# MIPI.net
KiCad netlist of a schematic drawn in Altium Designer
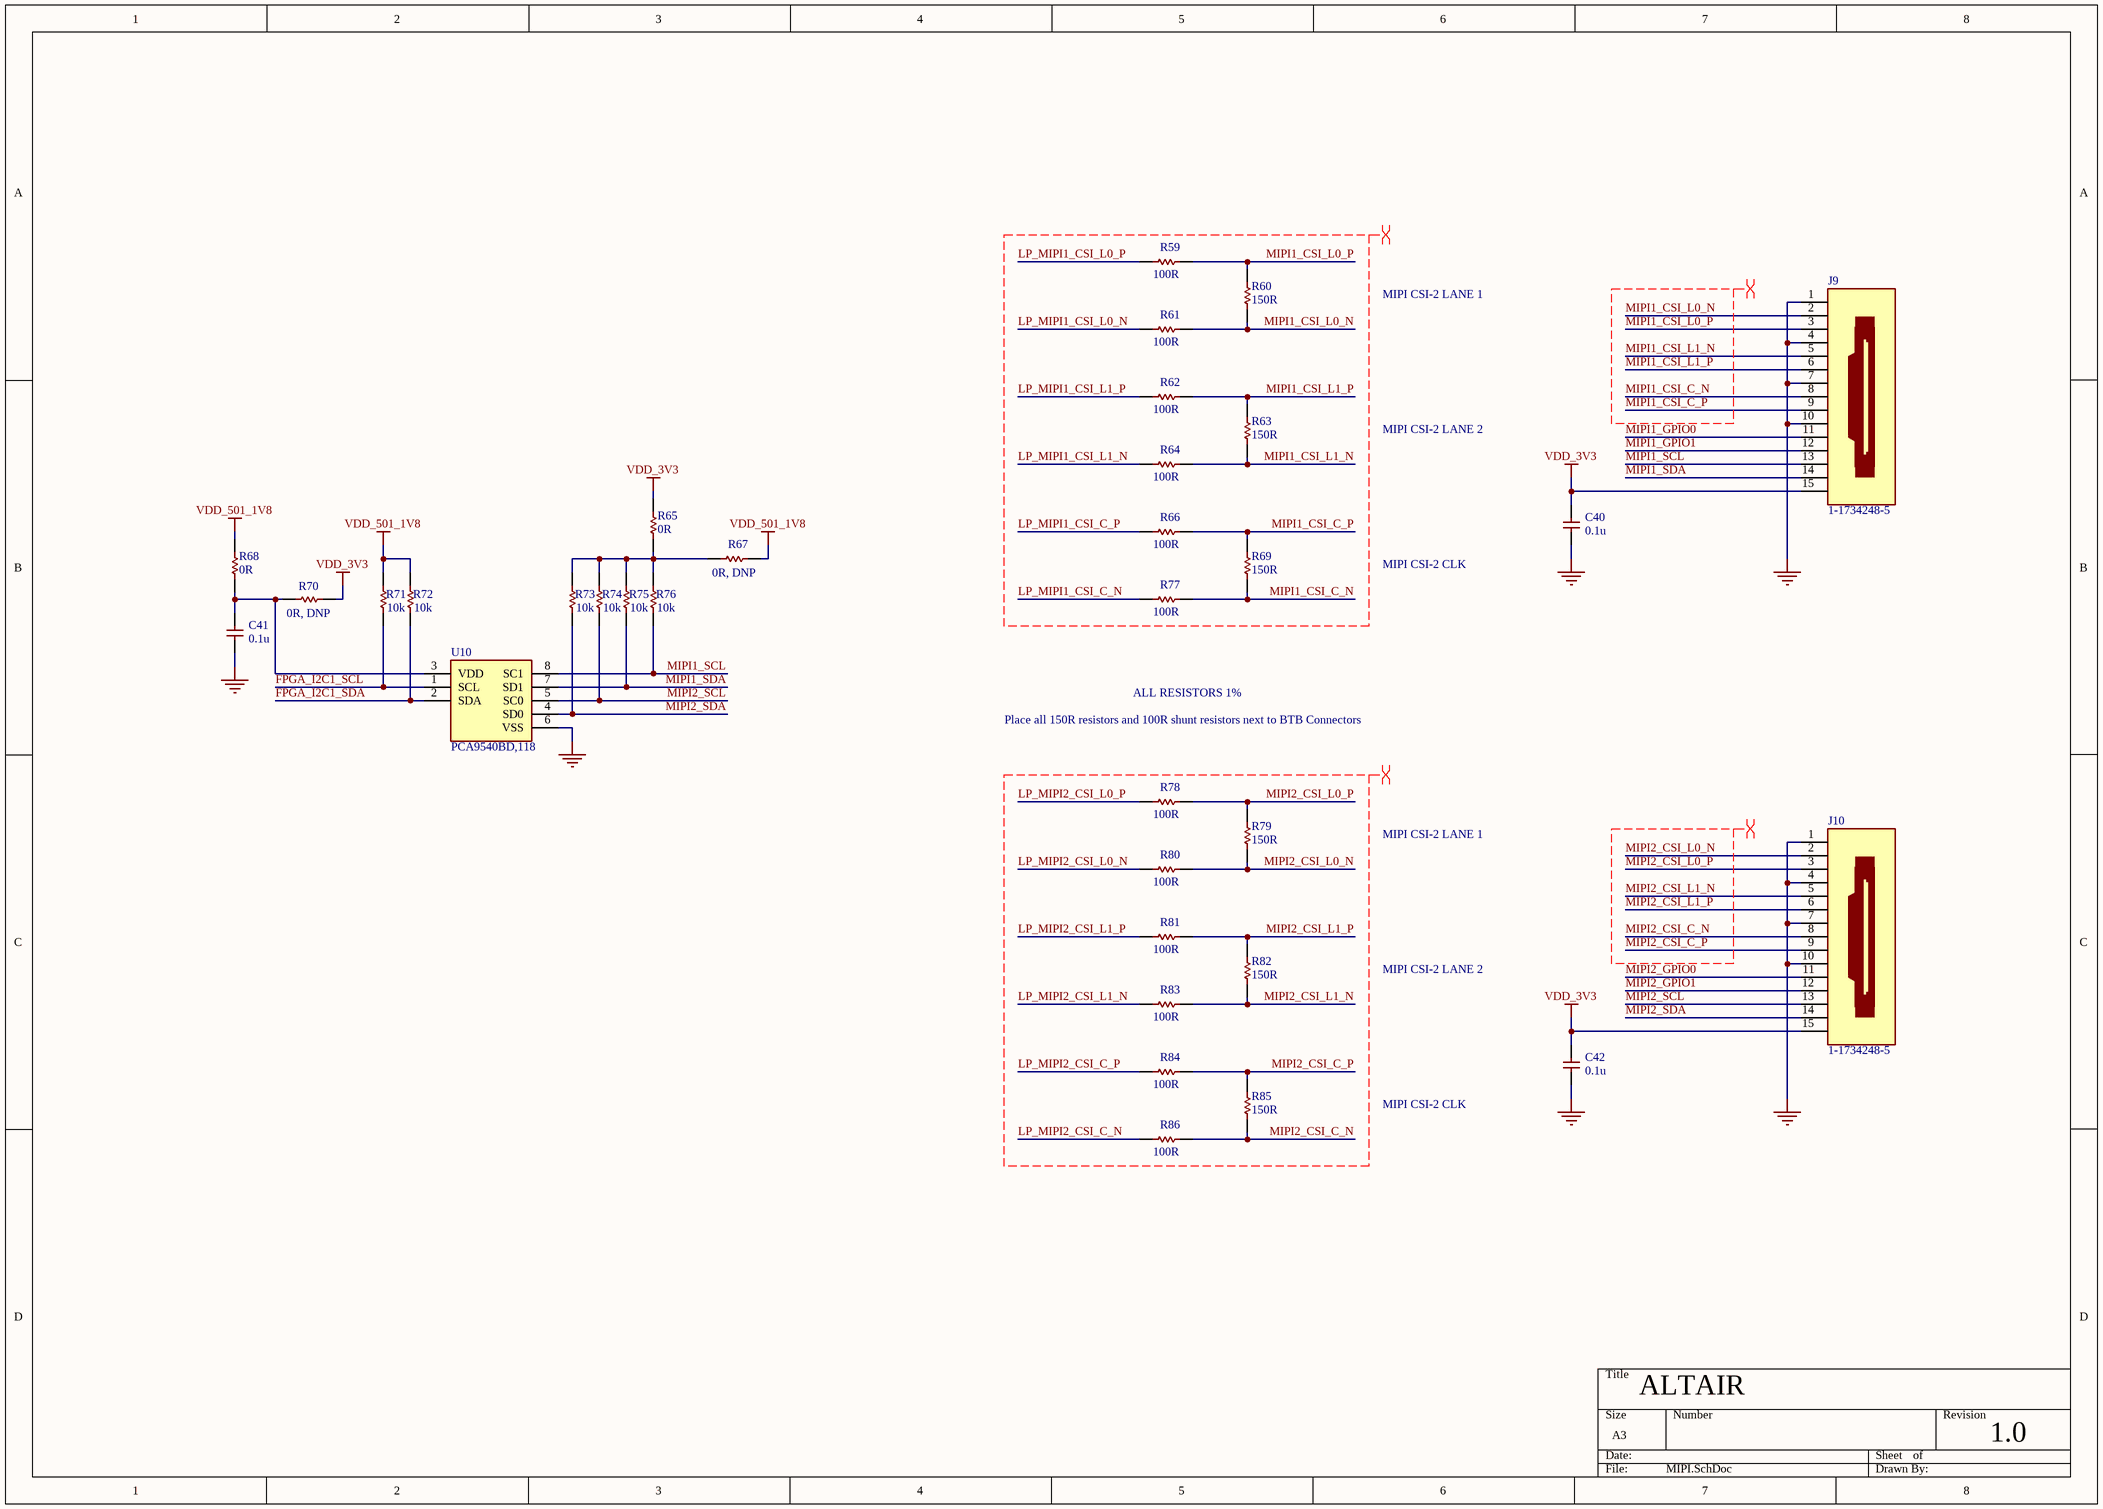
[diagram p0: MIPI.SchDoc]

(export (version "E")
  (design (tool "Eeschema 10.0.6"))
  (components
    (comp (ref "C40")
      (value "0.1u")
      (footprint "CAP_0402")
      (description "Capacitor SMD 0402")
      (fields (field (name "PART NO") "CL05B104KO5NNNC") (field (name "JLCPCB PART #") "C338112"))
      (libsource (lib "personalGenericLib") (part "CAP_0402"))
    )
    (comp (ref "C41")
      (value "0.1u")
      (footprint "CAP_0402")
      (description "Capacitor SMD 0402")
      (fields (field (name "PART NO") "CL05B104KO5NNNC") (field (name "JLCPCB PART #") "C338112"))
      (libsource (lib "personalGenericLib") (part "CAP_0402"))
    )
    (comp (ref "C42")
      (value "0.1u")
      (footprint "CAP_0402")
      (description "Capacitor SMD 0402")
      (fields (field (name "PART NO") "CL05B104KO5NNNC") (field (name "JLCPCB PART #") "C338112"))
      (libsource (lib "personalGenericLib") (part "CAP_0402"))
    )
    (comp (ref "J9")
      (value "1-1734248-5")
      (footprint "FP-1-1734248-5-MFG")
      (description "FPC CONNECTOR VERT 15 PINS 1.00MM SMD")
      (fields (field (name "JLCPCB PART #") "C2922285"))
      (libsource (lib "personalGenericLib") (part "1-1734248-5"))
    )
    (comp (ref "J10")
      (value "1-1734248-5")
      (footprint "FP-1-1734248-5-MFG")
      (description "FPC CONNECTOR VERT 15 PINS 1.00MM SMD")
      (fields (field (name "JLCPCB PART #") "C2922285"))
      (libsource (lib "personalGenericLib") (part "1-1734248-5"))
    )
    (comp (ref "R59")
      (value "100R")
      (footprint "RES_0402")
      (description "Resistor SMD 0402")
      (fields (field (name "JLCPCB PART #") "C106232") (field (name "PART NO") "RC0402FR-07100RL"))
      (libsource (lib "personalGenericLib") (part "RES_0402"))
    )
    (comp (ref "R60")
      (value "150R")
      (footprint "RES_0402")
      (description "Resistor SMD 0402")
      (fields (field (name "JLCPCB PART #") "C138054") (field (name "PART NO") "RC0402FR-07150RL"))
      (libsource (lib "personalGenericLib") (part "RES_0402"))
    )
    (comp (ref "R61")
      (value "100R")
      (footprint "RES_0402")
      (description "Resistor SMD 0402")
      (fields (field (name "JLCPCB PART #") "C106232") (field (name "PART NO") "RC0402FR-07100RL"))
      (libsource (lib "personalGenericLib") (part "RES_0402"))
    )
    (comp (ref "R62")
      (value "100R")
      (footprint "RES_0402")
      (description "Resistor SMD 0402")
      (fields (field (name "JLCPCB PART #") "C106232") (field (name "PART NO") "RC0402FR-07100RL"))
      (libsource (lib "personalGenericLib") (part "RES_0402"))
    )
    (comp (ref "R63")
      (value "150R")
      (footprint "RES_0402")
      (description "Resistor SMD 0402")
      (fields (field (name "JLCPCB PART #") "C138054") (field (name "PART NO") "RC0402FR-07150RL"))
      (libsource (lib "personalGenericLib") (part "RES_0402"))
    )
    (comp (ref "R64")
      (value "100R")
      (footprint "RES_0402")
      (description "Resistor SMD 0402")
      (fields (field (name "JLCPCB PART #") "C106232") (field (name "PART NO") "RC0402FR-07100RL"))
      (libsource (lib "personalGenericLib") (part "RES_0402"))
    )
    (comp (ref "R65")
      (value "0R")
      (footprint "RES_0402")
      (description "Resistor SMD 0402")
      (fields (field (name "JLCPCB PART #") "C60485") (field (name "PART NO") "RC0402JR-070RL"))
      (libsource (lib "personalGenericLib") (part "RES_0402"))
    )
    (comp (ref "R66")
      (value "100R")
      (footprint "RES_0402")
      (description "Resistor SMD 0402")
      (fields (field (name "JLCPCB PART #") "C106232") (field (name "PART NO") "RC0402FR-07100RL"))
      (libsource (lib "personalGenericLib") (part "RES_0402"))
    )
    (comp (ref "R67")
      (value "0R, DNP")
      (footprint "RES_0402")
      (description "Resistor SMD 0402")
      (fields (field (name "JLCPCB PART #") "C60485") (field (name "PART NO") "RC0402JR-070RL"))
      (libsource (lib "personalGenericLib") (part "RES_0402"))
    )
    (comp (ref "R68")
      (value "0R")
      (footprint "RES_0402")
      (description "Resistor SMD 0402")
      (fields (field (name "JLCPCB PART #") "C60485") (field (name "PART NO") "RC0402JR-070RL"))
      (libsource (lib "personalGenericLib") (part "RES_0402"))
    )
    (comp (ref "R69")
      (value "150R")
      (footprint "RES_0402")
      (description "Resistor SMD 0402")
      (fields (field (name "JLCPCB PART #") "C138054") (field (name "PART NO") "RC0402FR-07150RL"))
      (libsource (lib "personalGenericLib") (part "RES_0402"))
    )
    (comp (ref "R70")
      (value "0R, DNP")
      (footprint "RES_0402")
      (description "Resistor SMD 0402")
      (fields (field (name "JLCPCB PART #") "C60485") (field (name "PART NO") "RC0402JR-070RL"))
      (libsource (lib "personalGenericLib") (part "RES_0402"))
    )
    (comp (ref "R71")
      (value "10k")
      (footprint "RES_0402")
      (description "Resistor SMD 0402")
      (fields (field (name "JLCPCB PART #") "C60489") (field (name "PART NO") "RC0402JR-0710KL"))
      (libsource (lib "personalGenericLib") (part "RES_0402"))
    )
    (comp (ref "R72")
      (value "10k")
      (footprint "RES_0402")
      (description "Resistor SMD 0402")
      (fields (field (name "JLCPCB PART #") "C60489") (field (name "PART NO") "RC0402JR-0710KL"))
      (libsource (lib "personalGenericLib") (part "RES_0402"))
    )
    (comp (ref "R73")
      (value "10k")
      (footprint "RES_0402")
      (description "Resistor SMD 0402")
      (fields (field (name "JLCPCB PART #") "C60489") (field (name "PART NO") "RC0402JR-0710KL"))
      (libsource (lib "personalGenericLib") (part "RES_0402"))
    )
    (comp (ref "R74")
      (value "10k")
      (footprint "RES_0402")
      (description "Resistor SMD 0402")
      (fields (field (name "JLCPCB PART #") "C60489") (field (name "PART NO") "RC0402JR-0710KL"))
      (libsource (lib "personalGenericLib") (part "RES_0402"))
    )
    (comp (ref "R75")
      (value "10k")
      (footprint "RES_0402")
      (description "Resistor SMD 0402")
      (fields (field (name "JLCPCB PART #") "C60489") (field (name "PART NO") "RC0402JR-0710KL"))
      (libsource (lib "personalGenericLib") (part "RES_0402"))
    )
    (comp (ref "R76")
      (value "10k")
      (footprint "RES_0402")
      (description "Resistor SMD 0402")
      (fields (field (name "JLCPCB PART #") "C60489") (field (name "PART NO") "RC0402JR-0710KL"))
      (libsource (lib "personalGenericLib") (part "RES_0402"))
    )
    (comp (ref "R77")
      (value "100R")
      (footprint "RES_0402")
      (description "Resistor SMD 0402")
      (fields (field (name "JLCPCB PART #") "C106232") (field (name "PART NO") "RC0402FR-07100RL"))
      (libsource (lib "personalGenericLib") (part "RES_0402"))
    )
    (comp (ref "R78")
      (value "100R")
      (footprint "RES_0402")
      (description "Resistor SMD 0402")
      (fields (field (name "JLCPCB PART #") "C106232") (field (name "PART NO") "RC0402FR-07100RL"))
      (libsource (lib "personalGenericLib") (part "RES_0402"))
    )
    (comp (ref "R79")
      (value "150R")
      (footprint "RES_0402")
      (description "Resistor SMD 0402")
      (fields (field (name "JLCPCB PART #") "C138054") (field (name "PART NO") "RC0402FR-07150RL"))
      (libsource (lib "personalGenericLib") (part "RES_0402"))
    )
    (comp (ref "R80")
      (value "100R")
      (footprint "RES_0402")
      (description "Resistor SMD 0402")
      (fields (field (name "JLCPCB PART #") "C106232") (field (name "PART NO") "RC0402FR-07100RL"))
      (libsource (lib "personalGenericLib") (part "RES_0402"))
    )
    (comp (ref "R81")
      (value "100R")
      (footprint "RES_0402")
      (description "Resistor SMD 0402")
      (fields (field (name "JLCPCB PART #") "C106232") (field (name "PART NO") "RC0402FR-07100RL"))
      (libsource (lib "personalGenericLib") (part "RES_0402"))
    )
    (comp (ref "R82")
      (value "150R")
      (footprint "RES_0402")
      (description "Resistor SMD 0402")
      (fields (field (name "JLCPCB PART #") "C138054") (field (name "PART NO") "RC0402FR-07150RL"))
      (libsource (lib "personalGenericLib") (part "RES_0402"))
    )
    (comp (ref "R83")
      (value "100R")
      (footprint "RES_0402")
      (description "Resistor SMD 0402")
      (fields (field (name "JLCPCB PART #") "C106232") (field (name "PART NO") "RC0402FR-07100RL"))
      (libsource (lib "personalGenericLib") (part "RES_0402"))
    )
    (comp (ref "R84")
      (value "100R")
      (footprint "RES_0402")
      (description "Resistor SMD 0402")
      (fields (field (name "JLCPCB PART #") "C106232") (field (name "PART NO") "RC0402FR-07100RL"))
      (libsource (lib "personalGenericLib") (part "RES_0402"))
    )
    (comp (ref "R85")
      (value "150R")
      (footprint "RES_0402")
      (description "Resistor SMD 0402")
      (fields (field (name "JLCPCB PART #") "C138054") (field (name "PART NO") "RC0402FR-07150RL"))
      (libsource (lib "personalGenericLib") (part "RES_0402"))
    )
    (comp (ref "R86")
      (value "100R")
      (footprint "RES_0402")
      (description "Resistor SMD 0402")
      (fields (field (name "JLCPCB PART #") "C106232") (field (name "PART NO") "RC0402FR-07100RL"))
      (libsource (lib "personalGenericLib") (part "RES_0402"))
    )
    (comp (ref "U10")
      (value "PCA9540BD,118")
      (footprint "SOIC127P600X175-8N")
      (description "Integrated Circuit")
      (fields (field (name "JLCPCB PART #") "C2674107"))
      (libsource (lib "personalGenericLib") (part "PCA9540BD,118"))
    )
  )
  (nets
    (net (code "1") (name "/FPGA_I2C1_SCL") (class "Default")
      (node (ref "R71") (pin "2") (pinfunction "2_2") (pintype "passive"))
      (node (ref "U10") (pin "1") (pinfunction "SCL_1") (pintype "passive"))
    )
    (net (code "2") (name "/FPGA_I2C1_SDA") (class "Default")
      (node (ref "R72") (pin "2") (pinfunction "2_2") (pintype "passive"))
      (node (ref "U10") (pin "2") (pinfunction "SDA_2") (pintype "passive"))
    )
    (net (code "3") (name "/LP_MIPI1_CSI_C_N") (class "Default")
      (node (ref "R77") (pin "1") (pinfunction "1_1") (pintype "passive"))
    )
    (net (code "4") (name "/LP_MIPI1_CSI_C_P") (class "Default")
      (node (ref "R66") (pin "1") (pinfunction "1_1") (pintype "passive"))
    )
    (net (code "5") (name "/LP_MIPI1_CSI_L0_N") (class "Default")
      (node (ref "R61") (pin "1") (pinfunction "1_1") (pintype "passive"))
    )
    (net (code "6") (name "/LP_MIPI1_CSI_L0_P") (class "Default")
      (node (ref "R59") (pin "1") (pinfunction "1_1") (pintype "passive"))
    )
    (net (code "7") (name "/LP_MIPI1_CSI_L1_N") (class "Default")
      (node (ref "R64") (pin "1") (pinfunction "1_1") (pintype "passive"))
    )
    (net (code "8") (name "/LP_MIPI1_CSI_L1_P") (class "Default")
      (node (ref "R62") (pin "1") (pinfunction "1_1") (pintype "passive"))
    )
    (net (code "9") (name "/LP_MIPI2_CSI_C_N") (class "Default")
      (node (ref "R86") (pin "1") (pinfunction "1_1") (pintype "passive"))
    )
    (net (code "10") (name "/LP_MIPI2_CSI_C_P") (class "Default")
      (node (ref "R84") (pin "1") (pinfunction "1_1") (pintype "passive"))
    )
    (net (code "11") (name "/LP_MIPI2_CSI_L0_N") (class "Default")
      (node (ref "R80") (pin "1") (pinfunction "1_1") (pintype "passive"))
    )
    (net (code "12") (name "/LP_MIPI2_CSI_L0_P") (class "Default")
      (node (ref "R78") (pin "1") (pinfunction "1_1") (pintype "passive"))
    )
    (net (code "13") (name "/LP_MIPI2_CSI_L1_N") (class "Default")
      (node (ref "R83") (pin "1") (pinfunction "1_1") (pintype "passive"))
    )
    (net (code "14") (name "/LP_MIPI2_CSI_L1_P") (class "Default")
      (node (ref "R81") (pin "1") (pinfunction "1_1") (pintype "passive"))
    )
    (net (code "15") (name "/MIPI1_CSI_C_N") (class "Default")
      (node (ref "J9") (pin "8") (pinfunction "8_8") (pintype "passive"))
      (node (ref "R69") (pin "2") (pinfunction "2_2") (pintype "passive"))
      (node (ref "R77") (pin "2") (pinfunction "2_2") (pintype "passive"))
    )
    (net (code "16") (name "/MIPI1_CSI_C_P") (class "Default")
      (node (ref "J9") (pin "9") (pinfunction "9_9") (pintype "passive"))
      (node (ref "R66") (pin "2") (pinfunction "2_2") (pintype "passive"))
      (node (ref "R69") (pin "1") (pinfunction "1_1") (pintype "passive"))
    )
    (net (code "17") (name "/MIPI1_CSI_L0_N") (class "Default")
      (node (ref "J9") (pin "2") (pinfunction "2_2") (pintype "passive"))
      (node (ref "R60") (pin "2") (pinfunction "2_2") (pintype "passive"))
      (node (ref "R61") (pin "2") (pinfunction "2_2") (pintype "passive"))
    )
    (net (code "18") (name "/MIPI1_CSI_L0_P") (class "Default")
      (node (ref "J9") (pin "3") (pinfunction "3_3") (pintype "passive"))
      (node (ref "R59") (pin "2") (pinfunction "2_2") (pintype "passive"))
      (node (ref "R60") (pin "1") (pinfunction "1_1") (pintype "passive"))
    )
    (net (code "19") (name "/MIPI1_CSI_L1_N") (class "Default")
      (node (ref "J9") (pin "5") (pinfunction "5_5") (pintype "passive"))
      (node (ref "R63") (pin "2") (pinfunction "2_2") (pintype "passive"))
      (node (ref "R64") (pin "2") (pinfunction "2_2") (pintype "passive"))
    )
    (net (code "20") (name "/MIPI1_CSI_L1_P") (class "Default")
      (node (ref "J9") (pin "6") (pinfunction "6_6") (pintype "passive"))
      (node (ref "R62") (pin "2") (pinfunction "2_2") (pintype "passive"))
      (node (ref "R63") (pin "1") (pinfunction "1_1") (pintype "passive"))
    )
    (net (code "21") (name "/MIPI1_GPIO0") (class "Default")
      (node (ref "J9") (pin "11") (pinfunction "11_11") (pintype "passive"))
    )
    (net (code "22") (name "/MIPI1_GPIO1") (class "Default")
      (node (ref "J9") (pin "12") (pinfunction "12_12") (pintype "passive"))
    )
    (net (code "23") (name "/MIPI1_SCL") (class "Default")
      (node (ref "J9") (pin "13") (pinfunction "13_13") (pintype "passive"))
      (node (ref "R76") (pin "2") (pinfunction "2_2") (pintype "passive"))
      (node (ref "U10") (pin "8") (pinfunction "SC1_8") (pintype "passive"))
    )
    (net (code "24") (name "/MIPI1_SDA") (class "Default")
      (node (ref "J9") (pin "14") (pinfunction "14_14") (pintype "passive"))
      (node (ref "R75") (pin "2") (pinfunction "2_2") (pintype "passive"))
      (node (ref "U10") (pin "7") (pinfunction "SD1_7") (pintype "passive"))
    )
    (net (code "25") (name "/MIPI2_CSI_C_N") (class "Default")
      (node (ref "J10") (pin "8") (pinfunction "8_8") (pintype "passive"))
      (node (ref "R85") (pin "2") (pinfunction "2_2") (pintype "passive"))
      (node (ref "R86") (pin "2") (pinfunction "2_2") (pintype "passive"))
    )
    (net (code "26") (name "/MIPI2_CSI_C_P") (class "Default")
      (node (ref "J10") (pin "9") (pinfunction "9_9") (pintype "passive"))
      (node (ref "R84") (pin "2") (pinfunction "2_2") (pintype "passive"))
      (node (ref "R85") (pin "1") (pinfunction "1_1") (pintype "passive"))
    )
    (net (code "27") (name "/MIPI2_CSI_L0_N") (class "Default")
      (node (ref "J10") (pin "2") (pinfunction "2_2") (pintype "passive"))
      (node (ref "R79") (pin "2") (pinfunction "2_2") (pintype "passive"))
      (node (ref "R80") (pin "2") (pinfunction "2_2") (pintype "passive"))
    )
    (net (code "28") (name "/MIPI2_CSI_L0_P") (class "Default")
      (node (ref "J10") (pin "3") (pinfunction "3_3") (pintype "passive"))
      (node (ref "R78") (pin "2") (pinfunction "2_2") (pintype "passive"))
      (node (ref "R79") (pin "1") (pinfunction "1_1") (pintype "passive"))
    )
    (net (code "29") (name "/MIPI2_CSI_L1_N") (class "Default")
      (node (ref "J10") (pin "5") (pinfunction "5_5") (pintype "passive"))
      (node (ref "R82") (pin "2") (pinfunction "2_2") (pintype "passive"))
      (node (ref "R83") (pin "2") (pinfunction "2_2") (pintype "passive"))
    )
    (net (code "30") (name "/MIPI2_CSI_L1_P") (class "Default")
      (node (ref "J10") (pin "6") (pinfunction "6_6") (pintype "passive"))
      (node (ref "R81") (pin "2") (pinfunction "2_2") (pintype "passive"))
      (node (ref "R82") (pin "1") (pinfunction "1_1") (pintype "passive"))
    )
    (net (code "31") (name "/MIPI2_GPIO0") (class "Default")
      (node (ref "J10") (pin "11") (pinfunction "11_11") (pintype "passive"))
    )
    (net (code "32") (name "/MIPI2_GPIO1") (class "Default")
      (node (ref "J10") (pin "12") (pinfunction "12_12") (pintype "passive"))
    )
    (net (code "33") (name "/MIPI2_SCL") (class "Default")
      (node (ref "J10") (pin "13") (pinfunction "13_13") (pintype "passive"))
      (node (ref "R74") (pin "2") (pinfunction "2_2") (pintype "passive"))
      (node (ref "U10") (pin "5") (pinfunction "SC0_5") (pintype "passive"))
    )
    (net (code "34") (name "/MIPI2_SDA") (class "Default")
      (node (ref "J10") (pin "14") (pinfunction "14_14") (pintype "passive"))
      (node (ref "R73") (pin "2") (pinfunction "2_2") (pintype "passive"))
      (node (ref "U10") (pin "4") (pinfunction "SD0_4") (pintype "passive"))
    )
    (net (code "35") (name "GND") (class "Default")
      (node (ref "C40") (pin "1") (pinfunction "1_1") (pintype "passive"))
      (node (ref "C41") (pin "1") (pinfunction "1_1") (pintype "passive"))
      (node (ref "C42") (pin "1") (pinfunction "1_1") (pintype "passive"))
      (node (ref "J10") (pin "1") (pinfunction "1_1") (pintype "passive"))
      (node (ref "J10") (pin "10") (pinfunction "10_10") (pintype "passive"))
      (node (ref "J10") (pin "4") (pinfunction "4_4") (pintype "passive"))
      (node (ref "J10") (pin "7") (pinfunction "7_7") (pintype "passive"))
      (node (ref "J9") (pin "1") (pinfunction "1_1") (pintype "passive"))
      (node (ref "J9") (pin "10") (pinfunction "10_10") (pintype "passive"))
      (node (ref "J9") (pin "4") (pinfunction "4_4") (pintype "passive"))
      (node (ref "J9") (pin "7") (pinfunction "7_7") (pintype "passive"))
      (node (ref "U10") (pin "6") (pinfunction "VSS_6") (pintype "passive"))
    )
    (net (code "36") (name "Net-(R65-Pad1)") (class "Default")
      (node (ref "R65") (pin "1") (pinfunction "1_1") (pintype "passive"))
      (node (ref "R67") (pin "1") (pinfunction "1_1") (pintype "passive"))
      (node (ref "R73") (pin "1") (pinfunction "1_1") (pintype "passive"))
      (node (ref "R74") (pin "1") (pinfunction "1_1") (pintype "passive"))
      (node (ref "R75") (pin "1") (pinfunction "1_1") (pintype "passive"))
      (node (ref "R76") (pin "1") (pinfunction "1_1") (pintype "passive"))
    )
    (net (code "37") (name "Net-(U10-VDD)") (class "Default")
      (node (ref "C41") (pin "2") (pinfunction "2_2") (pintype "passive"))
      (node (ref "R68") (pin "1") (pinfunction "1_1") (pintype "passive"))
      (node (ref "R70") (pin "1") (pinfunction "1_1") (pintype "passive"))
      (node (ref "U10") (pin "3") (pinfunction "VDD_3") (pintype "passive"))
    )
    (net (code "38") (name "VDD_3V3") (class "Default")
      (node (ref "C40") (pin "2") (pinfunction "2_2") (pintype "passive"))
      (node (ref "C42") (pin "2") (pinfunction "2_2") (pintype "passive"))
      (node (ref "J10") (pin "15") (pinfunction "15_15") (pintype "passive"))
      (node (ref "J9") (pin "15") (pinfunction "15_15") (pintype "passive"))
      (node (ref "R65") (pin "2") (pinfunction "2_2") (pintype "passive"))
      (node (ref "R70") (pin "2") (pinfunction "2_2") (pintype "passive"))
    )
    (net (code "39") (name "VDD_501_1V8") (class "Default")
      (node (ref "R67") (pin "2") (pinfunction "2_2") (pintype "passive"))
      (node (ref "R68") (pin "2") (pinfunction "2_2") (pintype "passive"))
      (node (ref "R71") (pin "1") (pinfunction "1_1") (pintype "passive"))
      (node (ref "R72") (pin "1") (pinfunction "1_1") (pintype "passive"))
    )
  )
)
